# SH6_-_MICROCONTROLLER.net
KiCad netlist of a schematic drawn in Altium Designer
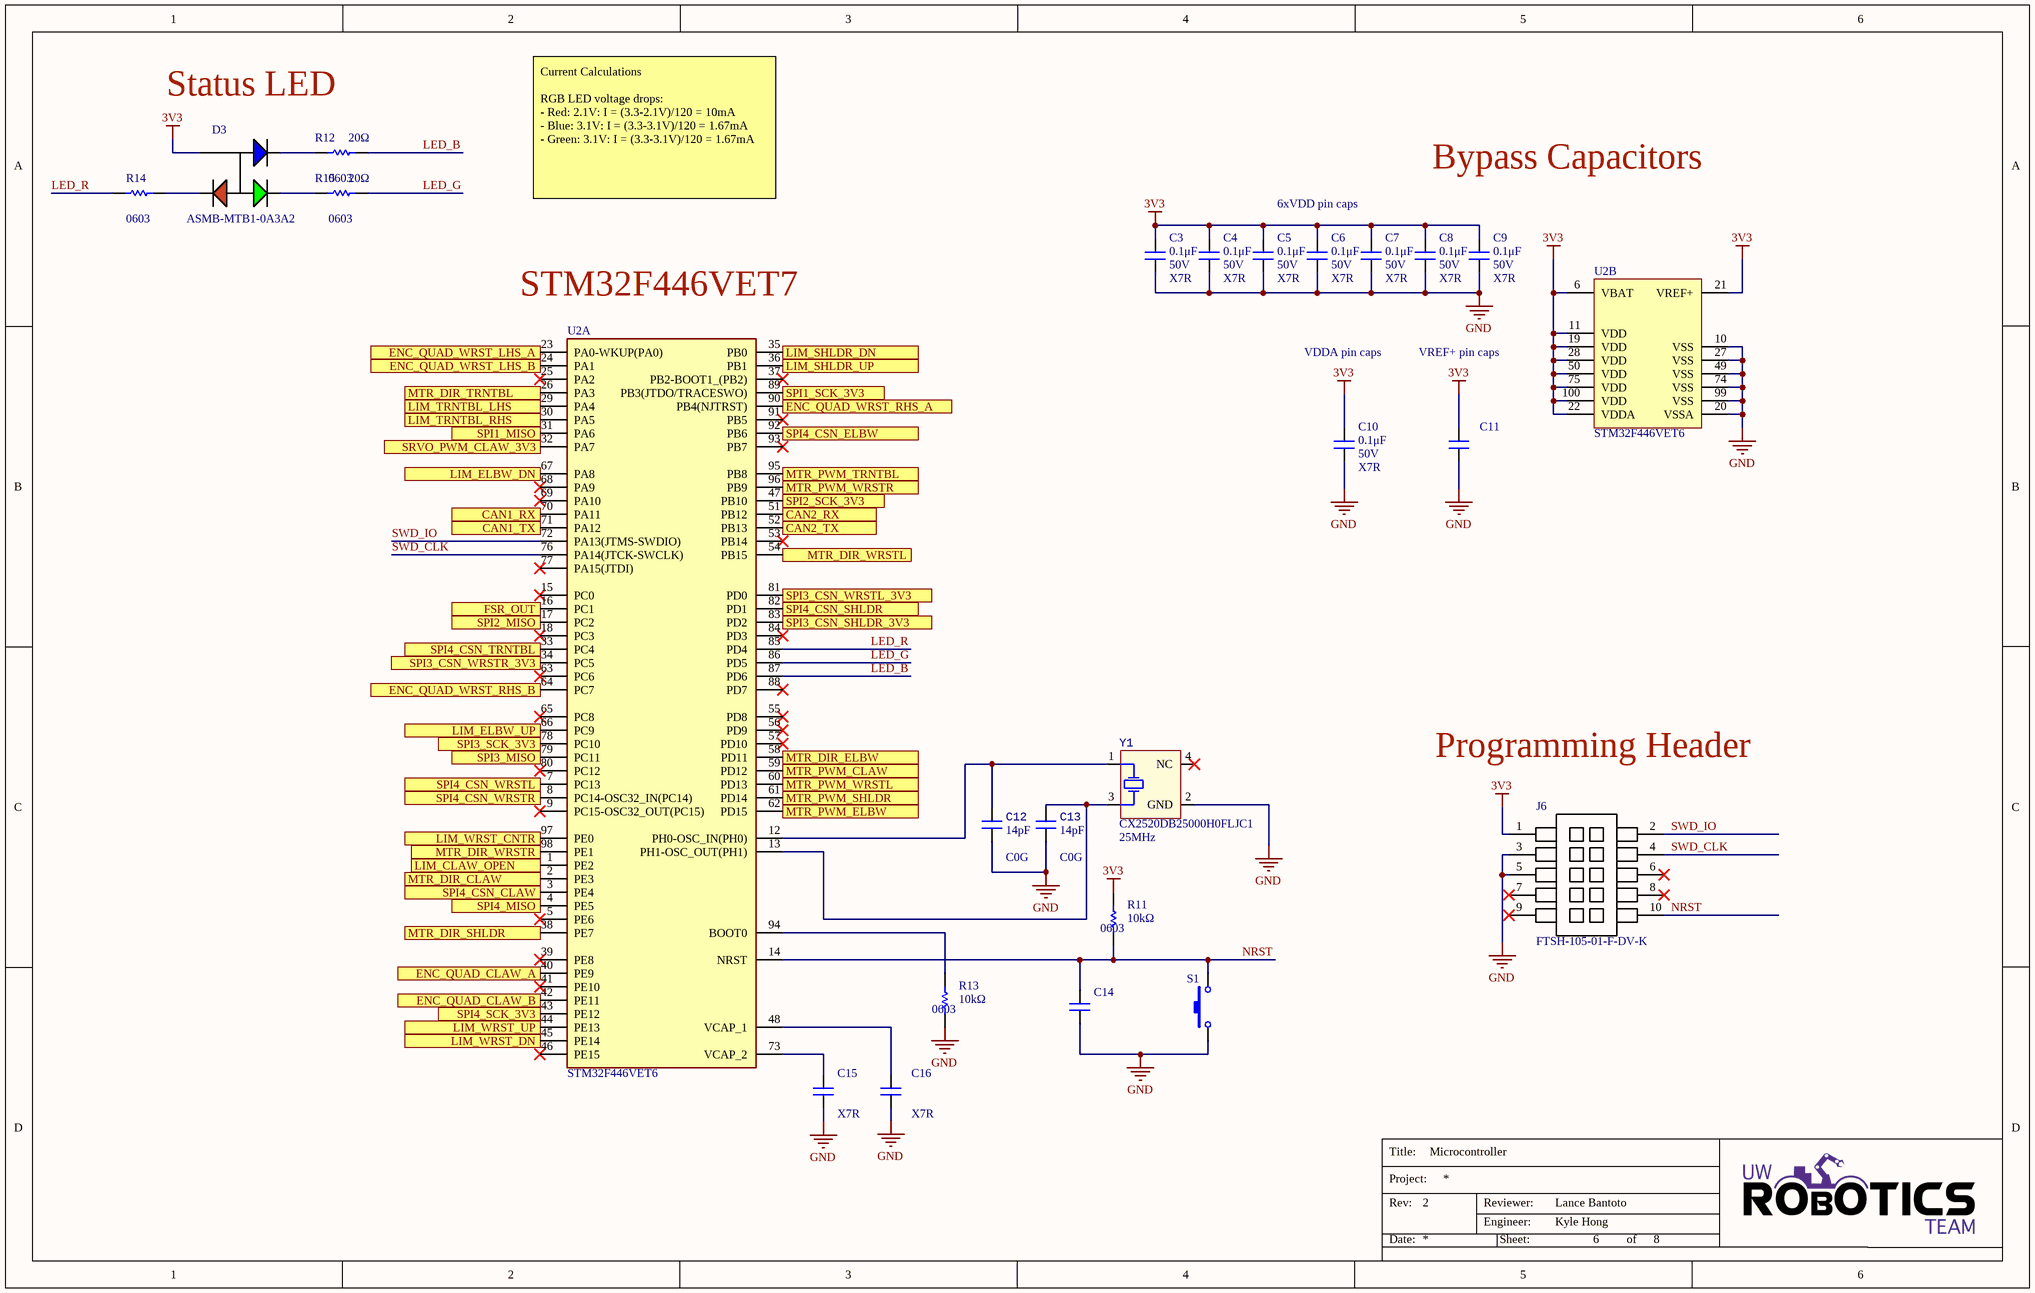
[diagram p0: SH6 - MICROCONTROLLER.SchDoc]

(export (version "E")
  (design (tool "Eeschema 10.0.6"))
  (components
    (comp (ref "C3")
      (value "0.1μF")
      (footprint "CAP0603")
      (description "CAP CER 0.1UF 50V X7R 0603")
      (fields
        (field (name "VOLTAGE RATING") "50V")
        (field (name "DIELECTRIC") "X7R")
        (field (name "Comment") "CAP_0.1uF_50V_0603")
      )
      (libsource (lib "UWRT_Schematic_Library_2020") (part "CAP_0.1uF_50V_0603"))
    )
    (comp (ref "C4")
      (value "0.1μF")
      (footprint "CAP0603")
      (description "CAP CER 0.1UF 50V X7R 0603")
      (fields
        (field (name "VOLTAGE RATING") "50V")
        (field (name "DIELECTRIC") "X7R")
        (field (name "Comment") "CAP_0.1uF_50V_0603")
      )
      (libsource (lib "UWRT_Schematic_Library_2020") (part "CAP_0.1uF_50V_0603"))
    )
    (comp (ref "C5")
      (value "0.1μF")
      (footprint "CAP0603")
      (description "CAP CER 0.1UF 50V X7R 0603")
      (fields
        (field (name "VOLTAGE RATING") "50V")
        (field (name "DIELECTRIC") "X7R")
        (field (name "Comment") "CAP_0.1uF_50V_0603")
      )
      (libsource (lib "UWRT_Schematic_Library_2020") (part "CAP_0.1uF_50V_0603"))
    )
    (comp (ref "C6")
      (value "0.1μF")
      (footprint "CAP0603")
      (description "CAP CER 0.1UF 50V X7R 0603")
      (fields
        (field (name "VOLTAGE RATING") "50V")
        (field (name "DIELECTRIC") "X7R")
        (field (name "Comment") "CAP_0.1uF_50V_0603")
      )
      (libsource (lib "UWRT_Schematic_Library_2020") (part "CAP_0.1uF_50V_0603"))
    )
    (comp (ref "C7")
      (value "0.1μF")
      (footprint "CAP0603")
      (description "CAP CER 0.1UF 50V X7R 0603")
      (fields
        (field (name "VOLTAGE RATING") "50V")
        (field (name "DIELECTRIC") "X7R")
        (field (name "Comment") "CAP_0.1uF_50V_0603")
      )
      (libsource (lib "UWRT_Schematic_Library_2020") (part "CAP_0.1uF_50V_0603"))
    )
    (comp (ref "C8")
      (value "0.1μF")
      (footprint "CAP0603")
      (description "CAP CER 0.1UF 50V X7R 0603")
      (fields
        (field (name "VOLTAGE RATING") "50V")
        (field (name "DIELECTRIC") "X7R")
        (field (name "Comment") "CAP_0.1uF_50V_0603")
      )
      (libsource (lib "UWRT_Schematic_Library_2020") (part "CAP_0.1uF_50V_0603"))
    )
    (comp (ref "C9")
      (value "0.1μF")
      (footprint "CAP0603")
      (description "CAP CER 0.1UF 50V X7R 0603")
      (fields
        (field (name "VOLTAGE RATING") "50V")
        (field (name "DIELECTRIC") "X7R")
        (field (name "Comment") "CAP_0.1uF_50V_0603")
      )
      (libsource (lib "UWRT_Schematic_Library_2020") (part "CAP_0.1uF_50V_0603"))
    )
    (comp (ref "C10")
      (value "0.1μF")
      (footprint "CAP0603")
      (description "CAP CER 0.1UF 50V X7R 0603")
      (fields
        (field (name "VOLTAGE RATING") "50V")
        (field (name "DIELECTRIC") "X7R")
        (field (name "Comment") "CAP_0.1uF_50V_0603")
      )
      (libsource (lib "UWRT_Schematic_Library_2020") (part "CAP_0.1uF_50V_0603"))
    )
    (comp (ref "C11")
      (value "CAP_1uF_25V_0603")
      (footprint "CAP0603")
      (description "CAP CER 1UF 25V X5R 0603")
      (libsource (lib "UWRT_Schematic_Library_2020") (part "CAP_1uF_25V_0603"))
    )
    (comp (ref "C12")
      (value "14pF")
      (footprint "CAP0603")
      (description "CAP CER 14PF 50V C0G/NP0 0603")
      (fields (field (name "DIELECTRIC") "C0G") (field (name "Comment") "CAP_14pF_50V_0603"))
      (libsource (lib "UWRT_Schematic_Library_2020") (part "CAP_14pF_50V_0603"))
    )
    (comp (ref "C13")
      (value "14pF")
      (footprint "CAP0603")
      (description "CAP CER 14PF 50V C0G/NP0 0603")
      (fields (field (name "DIELECTRIC") "C0G") (field (name "Comment") "CAP_14pF_50V_0603"))
      (libsource (lib "UWRT_Schematic_Library_2020") (part "CAP_14pF_50V_0603"))
    )
    (comp (ref "C14")
      (value "CAP_1uF_25V_0603")
      (footprint "CAP0603")
      (description "CAP CER 1UF 25V X5R 0603")
      (libsource (lib "UWRT_Schematic_Library_2020") (part "CAP_1uF_25V_0603"))
    )
    (comp (ref "C15")
      (value "CAP_4.7uF_50V_1206")
      (footprint "CAP1206")
      (description "CAP CER 4.7UF 50V X7R 1206")
      (fields (field (name "DIELECTRIC") "X7R"))
      (libsource (lib "UWRT_Schematic_Library_2020") (part "CAP_4.7uF_50V_1206"))
    )
    (comp (ref "C16")
      (value "CAP_4.7uF_50V_1206")
      (footprint "CAP1206")
      (description "CAP CER 4.7UF 50V X7R 1206")
      (fields (field (name "DIELECTRIC") "X7R"))
      (libsource (lib "UWRT_Schematic_Library_2020") (part "CAP_4.7uF_50V_1206"))
    )
    (comp (ref "D3")
      (value "LED_RGB")
      (footprint "LED_RGB")
      (description "LED RGB DIFFUSED 4PLCC SMD")
      (fields (field (name "MANUFACTURER PART NUMBER 1") "ASMB-MTB1-0A3A2"))
      (libsource (lib "UWRT_Schematic_Library_2020") (part "LED_RGB"))
    )
    (comp (ref "J6")
      (value "CON_PROGRAMMING")
      (footprint "FTSH-105-01-F-DV-K-P-TR")
      (description "CONN HEADER SMD 10POS 1.27MM")
      (fields (field (name "MANUFACTURER PART NUMBER 1") "FTSH-105-01-F-DV-K"))
      (libsource (lib "UWRT_Schematic_Library_2020") (part "CON_PROGRAMMING"))
    )
    (comp (ref "R11")
      (value "10kΩ")
      (footprint "RESC0603")
      (description "RES 10K OHM 5% 1/10W 0603")
      (fields (field (name "PACKAGE/FOOTPRINT") "0603") (field (name "Comment") "RES_10kΩ_0603_5%"))
      (libsource (lib "UWRT_Schematic_Library_2020") (part "RES_10kΩ_0603_5%"))
    )
    (comp (ref "R12")
      (value "20Ω")
      (footprint "RESC0603")
      (description "RES 20 OHM 5% 1/10W 0603")
      (fields (field (name "PACKAGE/FOOTPRINT") "0603") (field (name "Comment") "RES_20Ω_0603_5%"))
      (libsource (lib "UWRT_Schematic_Library_2020") (part "RES_20Ω_0603_5%"))
    )
    (comp (ref "R13")
      (value "10kΩ")
      (footprint "RESC0603")
      (description "RES 10K OHM 5% 1/10W 0603")
      (fields (field (name "PACKAGE/FOOTPRINT") "0603") (field (name "Comment") "RES_10kΩ_0603_5%"))
      (libsource (lib "UWRT_Schematic_Library_2020") (part "RES_10kΩ_0603_5%"))
    )
    (comp (ref "R14")
      (value "RES_120Ω_0603_5%_HP")
      (footprint "RESC0603")
      (description "RES 120 OHM 5% 1/4W 0603")
      (fields (field (name "PACKAGE/FOOTPRINT") "0603"))
      (libsource (lib "UWRT_Schematic_Library_2020") (part "RES_120Ω_0603_5%_HP"))
    )
    (comp (ref "R15")
      (value "20Ω")
      (footprint "RESC0603")
      (description "RES 20 OHM 5% 1/10W 0603")
      (fields (field (name "PACKAGE/FOOTPRINT") "0603") (field (name "Comment") "RES_20Ω_0603_5%"))
      (libsource (lib "UWRT_Schematic_Library_2020") (part "RES_20Ω_0603_5%"))
    )
    (comp (ref "S1")
      (value "SW_TACTILE")
      (footprint "B3U-1000P")
      (description "SWITCH TACTILE SPST-NO 0.05A 12V")
      (libsource (lib "UWRT_Schematic_Library_2020") (part "SW_TACTILE"))
    )
    (comp (ref "U2")
      (value "STM32F446VET6")
      (footprint "STM32F446VET6")
      (description "IC MCU 32BIT 512KB FLASH 100LQFP")
      (libsource (lib "UWRT_Schematic_Library_2020") (part "STM32F446VET6"))
    )
    (comp (ref "Y1")
      (value "CRYSTAL_25MHZ")
      (footprint "SOIC254P1016X440-4N")
      (description "CRYSTAL 25.0000MHZ 12PF SMD")
      (fields
        (field (name "MANUFACTURER PART NUMBER 1") "CX2520DB25000H0FLJC1")
        (field (name "FREQUENCY") "25MHz")
      )
      (libsource (lib "UWRT_Schematic_Library_2020") (part "CRYSTAL_25MHZ"))
    )
  )
  (nets
    (net (code "1") (name "/CAN1_RX") (class "Default")
      (node (ref "U2") (pin "70") (pinfunction "PA11_70") (pintype "passive"))
    )
    (net (code "2") (name "/CAN1_TX") (class "Default")
      (node (ref "U2") (pin "71") (pinfunction "PA12_71") (pintype "passive"))
    )
    (net (code "3") (name "/CAN2_RX") (class "Default")
      (node (ref "U2") (pin "51") (pinfunction "PB12_51") (pintype "passive"))
    )
    (net (code "4") (name "/CAN2_TX") (class "Default")
      (node (ref "U2") (pin "52") (pinfunction "PB13_52") (pintype "passive"))
    )
    (net (code "5") (name "/ENC_QUAD_CLAW_A") (class "Default")
      (node (ref "U2") (pin "40") (pinfunction "PE9_40") (pintype "passive"))
    )
    (net (code "6") (name "/ENC_QUAD_CLAW_B") (class "Default")
      (node (ref "U2") (pin "42") (pinfunction "PE11_42") (pintype "passive"))
    )
    (net (code "7") (name "/ENC_QUAD_WRST_LHS_A") (class "Default")
      (node (ref "U2") (pin "23") (pinfunction "PA0-WKUP(PA0)_23") (pintype "passive"))
    )
    (net (code "8") (name "/ENC_QUAD_WRST_LHS_B") (class "Default")
      (node (ref "U2") (pin "24") (pinfunction "PA1_24") (pintype "passive"))
    )
    (net (code "9") (name "/ENC_QUAD_WRST_RHS_A") (class "Default")
      (node (ref "U2") (pin "90") (pinfunction "PB4(NJTRST)_90") (pintype "passive"))
    )
    (net (code "10") (name "/ENC_QUAD_WRST_RHS_B") (class "Default")
      (node (ref "U2") (pin "64") (pinfunction "PC7_64") (pintype "passive"))
    )
    (net (code "11") (name "/FSR_OUT") (class "Default")
      (node (ref "U2") (pin "16") (pinfunction "PC1_16") (pintype "passive"))
    )
    (net (code "12") (name "/LED_B") (class "Default")
      (node (ref "R12") (pin "2") (pinfunction "2_2") (pintype "passive"))
      (node (ref "U2") (pin "87") (pinfunction "PD6_87") (pintype "passive"))
    )
    (net (code "13") (name "/LED_G") (class "Default")
      (node (ref "R15") (pin "2") (pinfunction "2_2") (pintype "passive"))
      (node (ref "U2") (pin "86") (pinfunction "PD5_86") (pintype "passive"))
    )
    (net (code "14") (name "/LED_R") (class "Default")
      (node (ref "R14") (pin "1") (pinfunction "1_1") (pintype "passive"))
      (node (ref "U2") (pin "85") (pinfunction "PD4_85") (pintype "passive"))
    )
    (net (code "15") (name "/LIM_CLAW_OPEN") (class "Default")
      (node (ref "U2") (pin "1") (pinfunction "PE2_1") (pintype "passive"))
    )
    (net (code "16") (name "/LIM_ELBW_DN") (class "Default")
      (node (ref "U2") (pin "67") (pinfunction "PA8_67") (pintype "passive"))
    )
    (net (code "17") (name "/LIM_ELBW_UP") (class "Default")
      (node (ref "U2") (pin "66") (pinfunction "PC9_66") (pintype "passive"))
    )
    (net (code "18") (name "/LIM_SHLDR_DN") (class "Default")
      (node (ref "U2") (pin "35") (pinfunction "PB0_35") (pintype "passive"))
    )
    (net (code "19") (name "/LIM_SHLDR_UP") (class "Default")
      (node (ref "U2") (pin "36") (pinfunction "PB1_36") (pintype "passive"))
    )
    (net (code "20") (name "/LIM_TRNTBL_LHS") (class "Default")
      (node (ref "U2") (pin "29") (pinfunction "PA4_29") (pintype "passive"))
    )
    (net (code "21") (name "/LIM_TRNTBL_RHS") (class "Default")
      (node (ref "U2") (pin "30") (pinfunction "PA5_30") (pintype "passive"))
    )
    (net (code "22") (name "/LIM_WRST_CNTR") (class "Default")
      (node (ref "U2") (pin "97") (pinfunction "PE0_97") (pintype "passive"))
    )
    (net (code "23") (name "/LIM_WRST_DN") (class "Default")
      (node (ref "U2") (pin "45") (pinfunction "PE14_45") (pintype "passive"))
    )
    (net (code "24") (name "/LIM_WRST_UP") (class "Default")
      (node (ref "U2") (pin "44") (pinfunction "PE13_44") (pintype "passive"))
    )
    (net (code "25") (name "/MTR_DIR_CLAW") (class "Default")
      (node (ref "U2") (pin "2") (pinfunction "PE3_2") (pintype "passive"))
    )
    (net (code "26") (name "/MTR_DIR_ELBW") (class "Default")
      (node (ref "U2") (pin "58") (pinfunction "PD11_58") (pintype "passive"))
    )
    (net (code "27") (name "/MTR_DIR_SHLDR") (class "Default")
      (node (ref "U2") (pin "38") (pinfunction "PE7_38") (pintype "passive"))
    )
    (net (code "28") (name "/MTR_DIR_TRNTBL") (class "Default")
      (node (ref "U2") (pin "26") (pinfunction "PA3_26") (pintype "passive"))
    )
    (net (code "29") (name "/MTR_DIR_WRSTL") (class "Default")
      (node (ref "U2") (pin "54") (pinfunction "PB15_54") (pintype "passive"))
    )
    (net (code "30") (name "/MTR_DIR_WRSTR") (class "Default")
      (node (ref "U2") (pin "98") (pinfunction "PE1_98") (pintype "passive"))
    )
    (net (code "31") (name "/MTR_PWM_CLAW") (class "Default")
      (node (ref "U2") (pin "59") (pinfunction "PD12_59") (pintype "passive"))
    )
    (net (code "32") (name "/MTR_PWM_ELBW") (class "Default")
      (node (ref "U2") (pin "62") (pinfunction "PD15_62") (pintype "passive"))
    )
    (net (code "33") (name "/MTR_PWM_SHLDR") (class "Default")
      (node (ref "U2") (pin "61") (pinfunction "PD14_61") (pintype "passive"))
    )
    (net (code "34") (name "/MTR_PWM_TRNTBL") (class "Default")
      (node (ref "U2") (pin "95") (pinfunction "PB8_95") (pintype "passive"))
    )
    (net (code "35") (name "/MTR_PWM_WRSTL") (class "Default")
      (node (ref "U2") (pin "60") (pinfunction "PD13_60") (pintype "passive"))
    )
    (net (code "36") (name "/MTR_PWM_WRSTR") (class "Default")
      (node (ref "U2") (pin "96") (pinfunction "PB9_96") (pintype "passive"))
    )
    (net (code "37") (name "/NRST") (class "Default")
      (node (ref "C14") (pin "2") (pinfunction "2_2") (pintype "passive"))
      (node (ref "J6") (pin "10") (pinfunction "10_10") (pintype "passive"))
      (node (ref "R11") (pin "2") (pinfunction "2_2") (pintype "passive"))
      (node (ref "S1") (pin "2") (pinfunction "2_2") (pintype "passive"))
      (node (ref "U2") (pin "14") (pinfunction "NRST_14") (pintype "passive"))
    )
    (net (code "38") (name "/SPI1_MISO") (class "Default")
      (node (ref "U2") (pin "31") (pinfunction "PA6_31") (pintype "passive"))
    )
    (net (code "39") (name "/SPI1_SCK_3V3") (class "Default")
      (node (ref "U2") (pin "89") (pinfunction "PB3(JTDO/TRACESWO)_89") (pintype "passive"))
    )
    (net (code "40") (name "/SPI2_MISO") (class "Default")
      (node (ref "U2") (pin "17") (pinfunction "PC2_17") (pintype "passive"))
    )
    (net (code "41") (name "/SPI2_SCK_3V3") (class "Default")
      (node (ref "U2") (pin "47") (pinfunction "PB10_47") (pintype "passive"))
    )
    (net (code "42") (name "/SPI3_CSN_SHLDR_3V3") (class "Default")
      (node (ref "U2") (pin "83") (pinfunction "PD2_83") (pintype "passive"))
    )
    (net (code "43") (name "/SPI3_CSN_WRSTL_3V3") (class "Default")
      (node (ref "U2") (pin "81") (pinfunction "PD0_81") (pintype "passive"))
    )
    (net (code "44") (name "/SPI3_CSN_WRSTR_3V3") (class "Default")
      (node (ref "U2") (pin "34") (pinfunction "PC5_34") (pintype "passive"))
    )
    (net (code "45") (name "/SPI3_MISO") (class "Default")
      (node (ref "U2") (pin "79") (pinfunction "PC11_79") (pintype "passive"))
    )
    (net (code "46") (name "/SPI3_SCK_3V3") (class "Default")
      (node (ref "U2") (pin "78") (pinfunction "PC10_78") (pintype "passive"))
    )
    (net (code "47") (name "/SPI4_CSN_CLAW") (class "Default")
      (node (ref "U2") (pin "3") (pinfunction "PE4_3") (pintype "passive"))
    )
    (net (code "48") (name "/SPI4_CSN_ELBW") (class "Default")
      (node (ref "U2") (pin "92") (pinfunction "PB6_92") (pintype "passive"))
    )
    (net (code "49") (name "/SPI4_CSN_SHLDR") (class "Default")
      (node (ref "U2") (pin "82") (pinfunction "PD1_82") (pintype "passive"))
    )
    (net (code "50") (name "/SPI4_CSN_TRNTBL") (class "Default")
      (node (ref "U2") (pin "33") (pinfunction "PC4_33") (pintype "passive"))
    )
    (net (code "51") (name "/SPI4_CSN_WRSTL") (class "Default")
      (node (ref "U2") (pin "7") (pinfunction "PC13_7") (pintype "passive"))
    )
    (net (code "52") (name "/SPI4_CSN_WRSTR") (class "Default")
      (node (ref "U2") (pin "8") (pinfunction "PC14-OSC32_IN(PC14)_8") (pintype "passive"))
    )
    (net (code "53") (name "/SPI4_MISO") (class "Default")
      (node (ref "U2") (pin "4") (pinfunction "PE5_4") (pintype "passive"))
    )
    (net (code "54") (name "/SPI4_SCK_3V3") (class "Default")
      (node (ref "U2") (pin "43") (pinfunction "PE12_43") (pintype "passive"))
    )
    (net (code "55") (name "/SRVO_PWM_CLAW_3V3") (class "Default")
      (node (ref "U2") (pin "32") (pinfunction "PA7_32") (pintype "passive"))
    )
    (net (code "56") (name "/SWD_CLK") (class "Default")
      (node (ref "J6") (pin "4") (pinfunction "4_4") (pintype "passive"))
      (node (ref "U2") (pin "76") (pinfunction "PA14(JTCK-SWCLK)_76") (pintype "passive"))
    )
    (net (code "57") (name "/SWD_IO") (class "Default")
      (node (ref "J6") (pin "2") (pinfunction "2_2") (pintype "passive"))
      (node (ref "U2") (pin "72") (pinfunction "PA13(JTMS-SWDIO)_72") (pintype "passive"))
    )
    (net (code "58") (name "3V3") (class "Default")
      (node (ref "C10") (pin "2") (pinfunction "2_2") (pintype "passive"))
      (node (ref "C11") (pin "2") (pinfunction "2_2") (pintype "passive"))
      (node (ref "C3") (pin "1") (pinfunction "1_1") (pintype "passive"))
      (node (ref "C4") (pin "1") (pinfunction "1_1") (pintype "passive"))
      (node (ref "C5") (pin "1") (pinfunction "1_1") (pintype "passive"))
      (node (ref "C6") (pin "1") (pinfunction "1_1") (pintype "passive"))
      (node (ref "C7") (pin "1") (pinfunction "1_1") (pintype "passive"))
      (node (ref "C8") (pin "1") (pinfunction "1_1") (pintype "passive"))
      (node (ref "C9") (pin "1") (pinfunction "1_1") (pintype "passive"))
      (node (ref "D3") (pin "4") (pinfunction "COMMON_ANODE_4") (pintype "passive"))
      (node (ref "J6") (pin "1") (pinfunction "1_1") (pintype "passive"))
      (node (ref "R11") (pin "1") (pinfunction "1_1") (pintype "passive"))
      (node (ref "U2") (pin "100") (pinfunction "VDD_100") (pintype "passive"))
      (node (ref "U2") (pin "11") (pinfunction "VDD_11") (pintype "passive"))
      (node (ref "U2") (pin "19") (pinfunction "VDD_19") (pintype "passive"))
      (node (ref "U2") (pin "21") (pinfunction "VREF+_21") (pintype "passive"))
      (node (ref "U2") (pin "22") (pinfunction "VDDA_22") (pintype "passive"))
      (node (ref "U2") (pin "28") (pinfunction "VDD_28") (pintype "passive"))
      (node (ref "U2") (pin "50") (pinfunction "VDD_50") (pintype "passive"))
      (node (ref "U2") (pin "6") (pinfunction "VBAT_6") (pintype "passive"))
      (node (ref "U2") (pin "75") (pinfunction "VDD_75") (pintype "passive"))
    )
    (net (code "59") (name "GND") (class "Default")
      (node (ref "C10") (pin "1") (pinfunction "1_1") (pintype "passive"))
      (node (ref "C11") (pin "1") (pinfunction "1_1") (pintype "passive"))
      (node (ref "C12") (pin "1") (pinfunction "1_1") (pintype "passive"))
      (node (ref "C13") (pin "1") (pinfunction "1_1") (pintype "passive"))
      (node (ref "C14") (pin "1") (pinfunction "1_1") (pintype "passive"))
      (node (ref "C15") (pin "1") (pinfunction "1_1") (pintype "passive"))
      (node (ref "C16") (pin "1") (pinfunction "1_1") (pintype "passive"))
      (node (ref "C3") (pin "2") (pinfunction "2_2") (pintype "passive"))
      (node (ref "C4") (pin "2") (pinfunction "2_2") (pintype "passive"))
      (node (ref "C5") (pin "2") (pinfunction "2_2") (pintype "passive"))
      (node (ref "C6") (pin "2") (pinfunction "2_2") (pintype "passive"))
      (node (ref "C7") (pin "2") (pinfunction "2_2") (pintype "passive"))
      (node (ref "C8") (pin "2") (pinfunction "2_2") (pintype "passive"))
      (node (ref "C9") (pin "2") (pinfunction "2_2") (pintype "passive"))
      (node (ref "J6") (pin "3") (pinfunction "3_3") (pintype "passive"))
      (node (ref "J6") (pin "5") (pinfunction "5_5") (pintype "passive"))
      (node (ref "R13") (pin "2") (pinfunction "2_2") (pintype "passive"))
      (node (ref "S1") (pin "1") (pinfunction "1_1") (pintype "passive"))
      (node (ref "U2") (pin "10") (pinfunction "VSS_10") (pintype "passive"))
      (node (ref "U2") (pin "20") (pinfunction "VSSA_20") (pintype "passive"))
      (node (ref "U2") (pin "27") (pinfunction "VSS_27") (pintype "passive"))
      (node (ref "U2") (pin "49") (pinfunction "VSS_49") (pintype "passive"))
      (node (ref "U2") (pin "74") (pinfunction "VSS_74") (pintype "passive"))
      (node (ref "U2") (pin "99") (pinfunction "VSS_99") (pintype "passive"))
      (node (ref "Y1") (pin "2") (pinfunction "GND_2") (pintype "power_in"))
    )
    (net (code "60") (name "Net-(D3-CATHODE_(BLUE))") (class "Default")
      (node (ref "D3") (pin "3") (pinfunction "CATHODE_(BLUE)_3") (pintype "passive"))
      (node (ref "R12") (pin "1") (pinfunction "1_1") (pintype "passive"))
    )
    (net (code "61") (name "Net-(D3-CATHODE_(GREEN))") (class "Default")
      (node (ref "D3") (pin "2") (pinfunction "CATHODE_(GREEN)_2") (pintype "passive"))
      (node (ref "R15") (pin "1") (pinfunction "1_1") (pintype "passive"))
    )
    (net (code "62") (name "Net-(D3-CATHODE_(RED))") (class "Default")
      (node (ref "D3") (pin "1") (pinfunction "CATHODE_(RED)_1") (pintype "passive"))
      (node (ref "R14") (pin "2") (pinfunction "2_2") (pintype "passive"))
    )
    (net (code "63") (name "Net-(U2A-BOOT0)") (class "Default")
      (node (ref "R13") (pin "1") (pinfunction "1_1") (pintype "passive"))
      (node (ref "U2") (pin "94") (pinfunction "BOOT0_94") (pintype "passive"))
    )
    (net (code "64") (name "Net-(U2A-PH0-OSC_IN(PH0))") (class "Default")
      (node (ref "C12") (pin "2") (pinfunction "2_2") (pintype "passive"))
      (node (ref "U2") (pin "12") (pinfunction "PH0-OSC_IN(PH0)_12") (pintype "passive"))
      (node (ref "Y1") (pin "1") (pinfunction "HOT_1") (pintype "passive"))
    )
    (net (code "65") (name "Net-(U2A-PH1-OSC_OUT(PH1))") (class "Default")
      (node (ref "C13") (pin "2") (pinfunction "2_2") (pintype "passive"))
      (node (ref "U2") (pin "13") (pinfunction "PH1-OSC_OUT(PH1)_13") (pintype "passive"))
      (node (ref "Y1") (pin "3") (pinfunction "HOT_3") (pintype "passive"))
    )
    (net (code "66") (name "Net-(U2A-VCAP_1)") (class "Default")
      (node (ref "C16") (pin "2") (pinfunction "2_2") (pintype "passive"))
      (node (ref "U2") (pin "48") (pinfunction "VCAP_1_48") (pintype "passive"))
    )
    (net (code "67") (name "Net-(U2A-VCAP_2)") (class "Default")
      (node (ref "C15") (pin "2") (pinfunction "2_2") (pintype "passive"))
      (node (ref "U2") (pin "73") (pinfunction "VCAP_2_73") (pintype "passive"))
    )
    (net (code "68") (name "unconnected-(J6-Pad6)") (class "Default")
      (node (ref "J6") (pin "6") (pinfunction "6_6") (pintype "passive+no_connect"))
    )
    (net (code "69") (name "unconnected-(J6-Pad7)") (class "Default")
      (node (ref "J6") (pin "7") (pinfunction "7_7") (pintype "passive+no_connect"))
    )
    (net (code "70") (name "unconnected-(J6-Pad8)") (class "Default")
      (node (ref "J6") (pin "8") (pinfunction "8_8") (pintype "passive+no_connect"))
    )
    (net (code "71") (name "unconnected-(J6-Pad9)") (class "Default")
      (node (ref "J6") (pin "9") (pinfunction "9_9") (pintype "passive+no_connect"))
    )
    (net (code "72") (name "unconnected-(U2A-PA2-Pad25)") (class "Default")
      (node (ref "U2") (pin "25") (pinfunction "PA2_25") (pintype "passive+no_connect"))
    )
    (net (code "73") (name "unconnected-(U2A-PA9-Pad68)") (class "Default")
      (node (ref "U2") (pin "68") (pinfunction "PA9_68") (pintype "passive+no_connect"))
    )
    (net (code "74") (name "unconnected-(U2A-PA10-Pad69)") (class "Default")
      (node (ref "U2") (pin "69") (pinfunction "PA10_69") (pintype "passive+no_connect"))
    )
    (net (code "75") (name "unconnected-(U2A-PA15(JTDI)-Pad77)") (class "Default")
      (node (ref "U2") (pin "77") (pinfunction "PA15(JTDI)_77") (pintype "passive+no_connect"))
    )
    (net (code "76") (name "unconnected-(U2A-PB2-BOOT1_(PB2)-Pad37)") (class "Default")
      (node (ref "U2") (pin "37") (pinfunction "PB2-BOOT1_(PB2)_37") (pintype "passive+no_connect"))
    )
    (net (code "77") (name "unconnected-(U2A-PB5-Pad91)") (class "Default")
      (node (ref "U2") (pin "91") (pinfunction "PB5_91") (pintype "passive+no_connect"))
    )
    (net (code "78") (name "unconnected-(U2A-PB7-Pad93)") (class "Default")
      (node (ref "U2") (pin "93") (pinfunction "PB7_93") (pintype "passive+no_connect"))
    )
    (net (code "79") (name "unconnected-(U2A-PB14-Pad53)") (class "Default")
      (node (ref "U2") (pin "53") (pinfunction "PB14_53") (pintype "passive+no_connect"))
    )
    (net (code "80") (name "unconnected-(U2A-PC0-Pad15)") (class "Default")
      (node (ref "U2") (pin "15") (pinfunction "PC0_15") (pintype "passive+no_connect"))
    )
    (net (code "81") (name "unconnected-(U2A-PC3-Pad18)") (class "Default")
      (node (ref "U2") (pin "18") (pinfunction "PC3_18") (pintype "passive+no_connect"))
    )
    (net (code "82") (name "unconnected-(U2A-PC6-Pad63)") (class "Default")
      (node (ref "U2") (pin "63") (pinfunction "PC6_63") (pintype "passive+no_connect"))
    )
    (net (code "83") (name "unconnected-(U2A-PC8-Pad65)") (class "Default")
      (node (ref "U2") (pin "65") (pinfunction "PC8_65") (pintype "passive+no_connect"))
    )
    (net (code "84") (name "unconnected-(U2A-PC12-Pad80)") (class "Default")
      (node (ref "U2") (pin "80") (pinfunction "PC12_80") (pintype "passive+no_connect"))
    )
    (net (code "85") (name "unconnected-(U2A-PC15-OSC32_OUT(PC15)-Pad9)") (class "Default")
      (node (ref "U2") (pin "9") (pinfunction "PC15-OSC32_OUT(PC15)_9") (pintype "passive+no_connect"))
    )
    (net (code "86") (name "unconnected-(U2A-PD3-Pad84)") (class "Default")
      (node (ref "U2") (pin "84") (pinfunction "PD3_84") (pintype "passive+no_connect"))
    )
    (net (code "87") (name "unconnected-(U2A-PD7-Pad88)") (class "Default")
      (node (ref "U2") (pin "88") (pinfunction "PD7_88") (pintype "passive+no_connect"))
    )
    (net (code "88") (name "unconnected-(U2A-PD8-Pad55)") (class "Default")
      (node (ref "U2") (pin "55") (pinfunction "PD8_55") (pintype "passive+no_connect"))
    )
    (net (code "89") (name "unconnected-(U2A-PD9-Pad56)") (class "Default")
      (node (ref "U2") (pin "56") (pinfunction "PD9_56") (pintype "passive+no_connect"))
    )
    (net (code "90") (name "unconnected-(U2A-PD10-Pad57)") (class "Default")
      (node (ref "U2") (pin "57") (pinfunction "PD10_57") (pintype "passive+no_connect"))
    )
    (net (code "91") (name "unconnected-(U2A-PE6-Pad5)") (class "Default")
      (node (ref "U2") (pin "5") (pinfunction "PE6_5") (pintype "passive+no_connect"))
    )
    (net (code "92") (name "unconnected-(U2A-PE8-Pad39)") (class "Default")
      (node (ref "U2") (pin "39") (pinfunction "PE8_39") (pintype "passive+no_connect"))
    )
    (net (code "93") (name "unconnected-(U2A-PE10-Pad41)") (class "Default")
      (node (ref "U2") (pin "41") (pinfunction "PE10_41") (pintype "passive+no_connect"))
    )
    (net (code "94") (name "unconnected-(U2A-PE15-Pad46)") (class "Default")
      (node (ref "U2") (pin "46") (pinfunction "PE15_46") (pintype "passive+no_connect"))
    )
    (net (code "95") (name "unconnected-(Y1-NC-Pad4)") (class "Default")
      (node (ref "Y1") (pin "4") (pinfunction "NC_4") (pintype "passive+no_connect"))
    )
  )
)
